# fcu-display.net
KiCad netlist of a schematic drawn in EAGLE
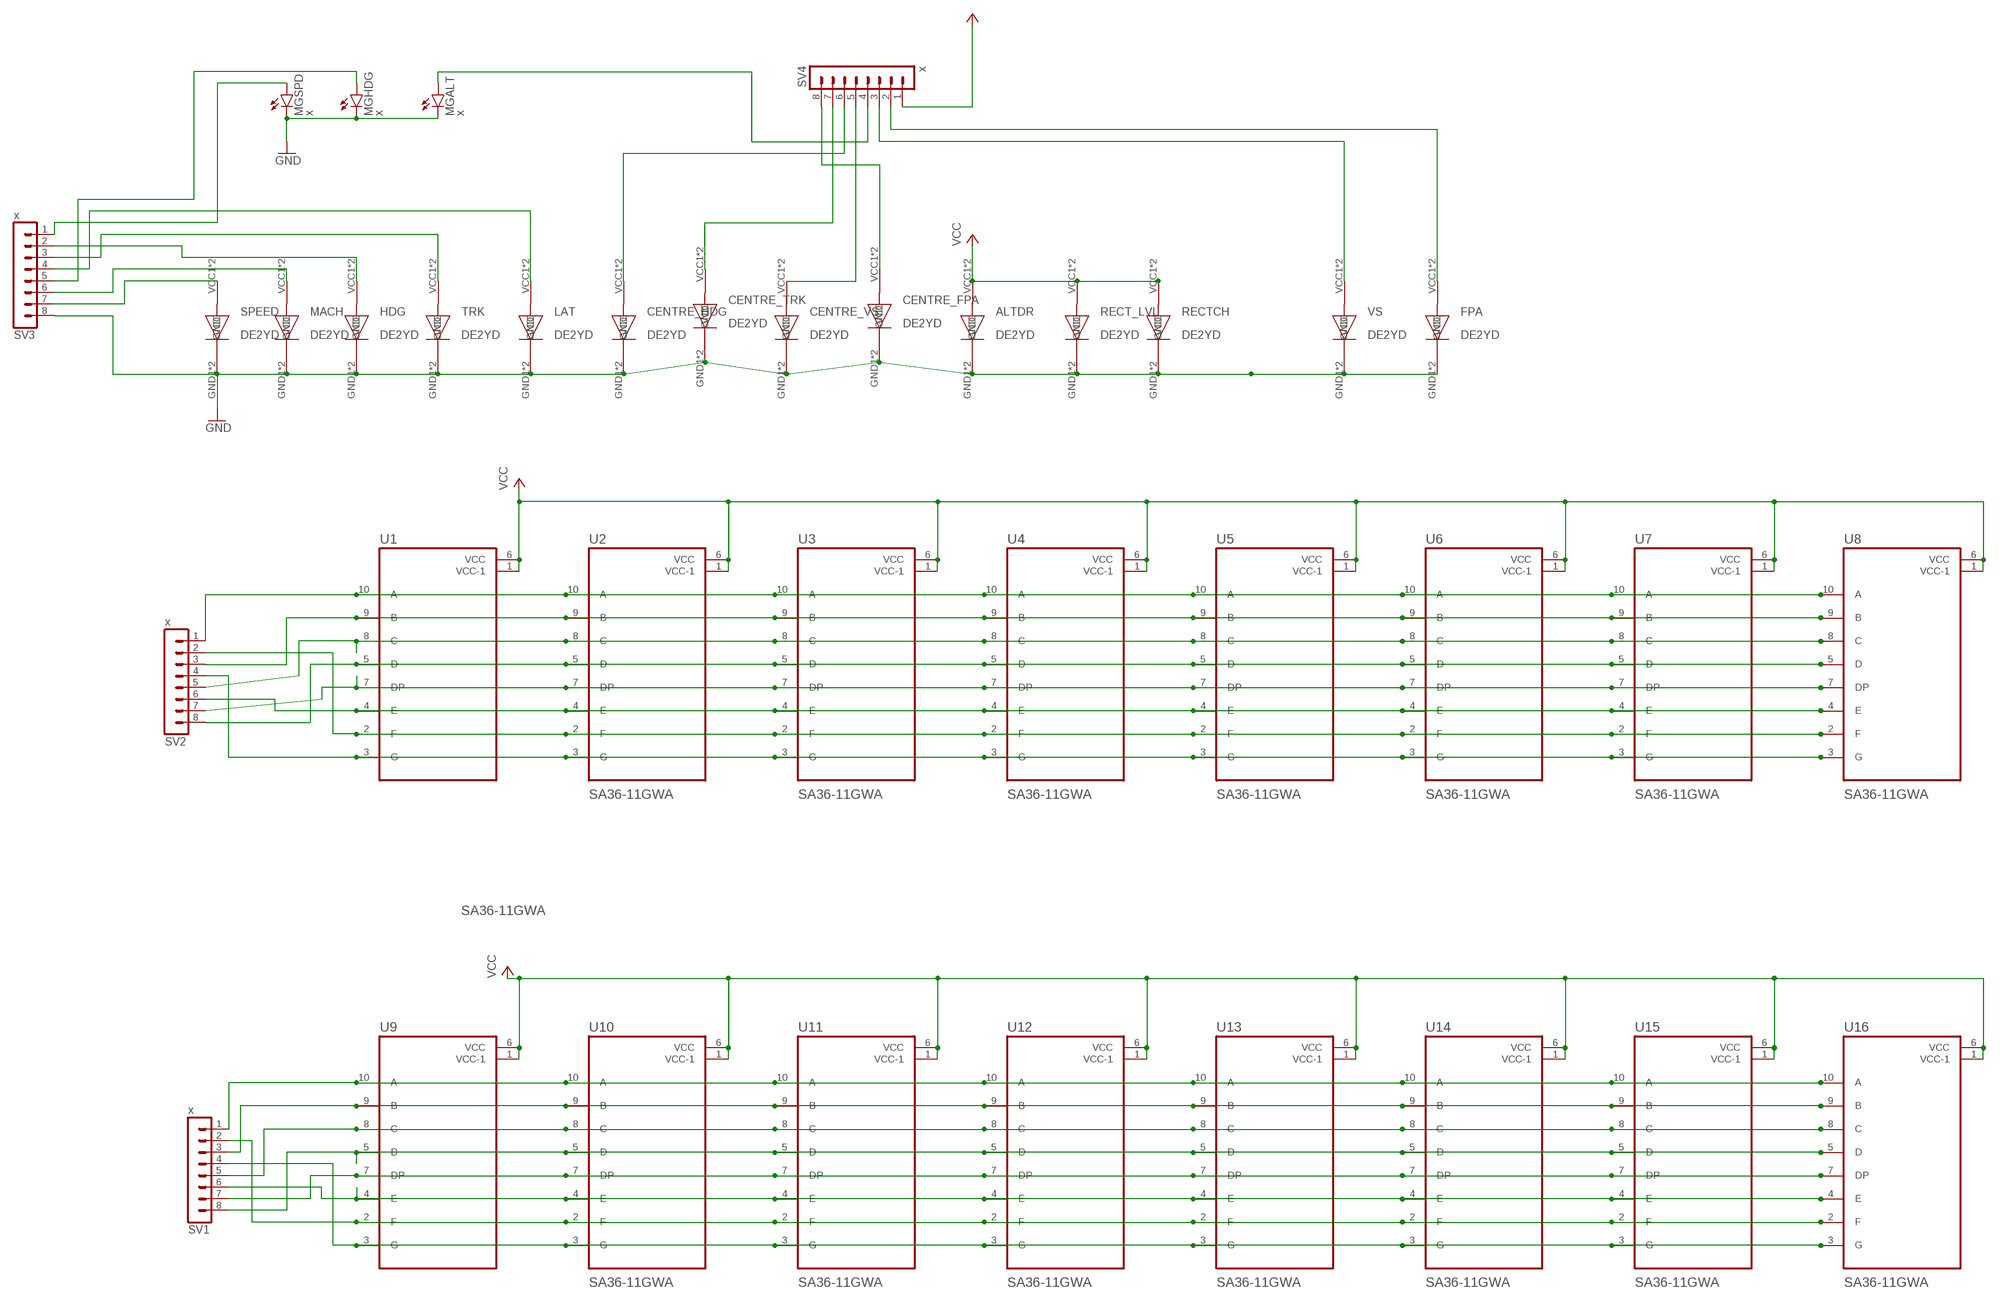
[diagram p0: schematic, sheet 1]

(export (version "E")
  (design (tool "Eeschema 10.0.6"))
  (components
    (comp (ref "ALTDR")
      (value "DE2YD")
      (footprint "eagle-import:STANDARD")
      (libsource (lib "eagle-import") (part "DE2YD"))
    )
    (comp (ref "CENTRE_FPA")
      (value "DE2YD")
      (footprint "eagle-import:STANDARD")
      (libsource (lib "eagle-import") (part "DE2YD"))
    )
    (comp (ref "CENTRE_HDG")
      (value "DE2YD")
      (footprint "eagle-import:STANDARD")
      (libsource (lib "eagle-import") (part "DE2YD"))
    )
    (comp (ref "CENTRE_TRK")
      (value "DE2YD")
      (footprint "eagle-import:STANDARD")
      (libsource (lib "eagle-import") (part "DE2YD"))
    )
    (comp (ref "CENTRE_VS")
      (value "DE2YD")
      (footprint "eagle-import:STANDARD")
      (libsource (lib "eagle-import") (part "DE2YD"))
    )
    (comp (ref "FPA")
      (value "DE2YD")
      (footprint "eagle-import:STANDARD")
      (libsource (lib "eagle-import") (part "DE2YD"))
    )
    (comp (ref "HDG")
      (value "DE2YD")
      (footprint "eagle-import:STANDARD")
      (libsource (lib "eagle-import") (part "DE2YD"))
    )
    (comp (ref "LAT")
      (value "DE2YD")
      (footprint "eagle-import:STANDARD")
      (libsource (lib "eagle-import") (part "DE2YD"))
    )
    (comp (ref "MACH")
      (value "DE2YD")
      (footprint "eagle-import:STANDARD")
      (libsource (lib "eagle-import") (part "DE2YD"))
    )
    (comp (ref "MGALT")
      (value "x")
      (footprint "eagle-import:LED3MM")
      (libsource (lib "eagle-import") (part "LED3MM"))
    )
    (comp (ref "MGHDG")
      (value "x")
      (footprint "eagle-import:LED3MM")
      (libsource (lib "eagle-import") (part "LED3MM"))
    )
    (comp (ref "MGSPD")
      (value "x")
      (footprint "eagle-import:LED3MM")
      (libsource (lib "eagle-import") (part "LED3MM"))
    )
    (comp (ref "RECTCH")
      (value "DE2YD")
      (footprint "eagle-import:STANDARD")
      (libsource (lib "eagle-import") (part "DE2YD"))
    )
    (comp (ref "RECT_LVL")
      (value "DE2YD")
      (footprint "eagle-import:STANDARD")
      (libsource (lib "eagle-import") (part "DE2YD"))
    )
    (comp (ref "SPEED")
      (value "DE2YD")
      (footprint "eagle-import:STANDARD")
      (libsource (lib "eagle-import") (part "DE2YD"))
    )
    (comp (ref "SV1")
      (value "x")
      (footprint "eagle-import:MA08-1")
      (libsource (lib "eagle-import") (part "MA08-1"))
    )
    (comp (ref "SV2")
      (value "x")
      (footprint "eagle-import:MA08-1")
      (libsource (lib "eagle-import") (part "MA08-1"))
    )
    (comp (ref "SV3")
      (value "x")
      (footprint "eagle-import:MA08-1")
      (libsource (lib "eagle-import") (part "MA08-1"))
    )
    (comp (ref "SV4")
      (value "x")
      (footprint "eagle-import:MA08-1")
      (libsource (lib "eagle-import") (part "MA08-1"))
    )
    (comp (ref "TRK")
      (value "DE2YD")
      (footprint "eagle-import:STANDARD")
      (libsource (lib "eagle-import") (part "DE2YD"))
    )
    (comp (ref "U1")
      (value "SA36-11GWA")
      (footprint "eagle-import:KINGBRIGHT_SC36-11SRWA")
      (fields (field (name "MF") "Kingbright"))
      (libsource (lib "eagle-import") (part "SA36-11GWA"))
    )
    (comp (ref "U2")
      (value "SA36-11GWA")
      (footprint "eagle-import:KINGBRIGHT_SC36-11SRWA")
      (fields (field (name "MF") "Kingbright"))
      (libsource (lib "eagle-import") (part "SA36-11GWA"))
    )
    (comp (ref "U3")
      (value "SA36-11GWA")
      (footprint "eagle-import:KINGBRIGHT_SC36-11SRWA")
      (fields (field (name "MF") "Kingbright"))
      (libsource (lib "eagle-import") (part "SA36-11GWA"))
    )
    (comp (ref "U4")
      (value "SA36-11GWA")
      (footprint "eagle-import:KINGBRIGHT_SC36-11SRWA")
      (fields (field (name "MF") "Kingbright"))
      (libsource (lib "eagle-import") (part "SA36-11GWA"))
    )
    (comp (ref "U5")
      (value "SA36-11GWA")
      (footprint "eagle-import:KINGBRIGHT_SC36-11SRWA")
      (fields (field (name "MF") "Kingbright"))
      (libsource (lib "eagle-import") (part "SA36-11GWA"))
    )
    (comp (ref "U6")
      (value "SA36-11GWA")
      (footprint "eagle-import:KINGBRIGHT_SC36-11SRWA")
      (fields (field (name "MF") "Kingbright"))
      (libsource (lib "eagle-import") (part "SA36-11GWA"))
    )
    (comp (ref "U7")
      (value "SA36-11GWA")
      (footprint "eagle-import:KINGBRIGHT_SC36-11SRWA")
      (fields (field (name "MF") "Kingbright"))
      (libsource (lib "eagle-import") (part "SA36-11GWA"))
    )
    (comp (ref "U8")
      (value "SA36-11GWA")
      (footprint "eagle-import:KINGBRIGHT_SC36-11SRWA")
      (fields (field (name "MF") "Kingbright"))
      (libsource (lib "eagle-import") (part "SA36-11GWA"))
    )
    (comp (ref "U9")
      (value "SA36-11GWA")
      (footprint "eagle-import:KINGBRIGHT_SC36-11SRWA")
      (fields (field (name "MF") "Kingbright"))
      (libsource (lib "eagle-import") (part "SA36-11GWA"))
    )
    (comp (ref "U10")
      (value "SA36-11GWA")
      (footprint "eagle-import:KINGBRIGHT_SC36-11SRWA")
      (fields (field (name "MF") "Kingbright"))
      (libsource (lib "eagle-import") (part "SA36-11GWA"))
    )
    (comp (ref "U11")
      (value "SA36-11GWA")
      (footprint "eagle-import:KINGBRIGHT_SC36-11SRWA")
      (fields (field (name "MF") "Kingbright"))
      (libsource (lib "eagle-import") (part "SA36-11GWA"))
    )
    (comp (ref "U12")
      (value "SA36-11GWA")
      (footprint "eagle-import:KINGBRIGHT_SC36-11SRWA")
      (fields (field (name "MF") "Kingbright"))
      (libsource (lib "eagle-import") (part "SA36-11GWA"))
    )
    (comp (ref "U13")
      (value "SA36-11GWA")
      (footprint "eagle-import:KINGBRIGHT_SC36-11SRWA")
      (fields (field (name "MF") "Kingbright"))
      (libsource (lib "eagle-import") (part "SA36-11GWA"))
    )
    (comp (ref "U14")
      (value "SA36-11GWA")
      (footprint "eagle-import:KINGBRIGHT_SC36-11SRWA")
      (fields (field (name "MF") "Kingbright"))
      (libsource (lib "eagle-import") (part "SA36-11GWA"))
    )
    (comp (ref "U15")
      (value "SA36-11GWA")
      (footprint "eagle-import:KINGBRIGHT_SC36-11SRWA")
      (fields (field (name "MF") "Kingbright"))
      (libsource (lib "eagle-import") (part "SA36-11GWA"))
    )
    (comp (ref "U16")
      (value "SA36-11GWA")
      (footprint "eagle-import:KINGBRIGHT_SC36-11SRWA")
      (fields (field (name "MF") "Kingbright"))
      (libsource (lib "eagle-import") (part "SA36-11GWA"))
    )
    (comp (ref "VS")
      (value "DE2YD")
      (footprint "eagle-import:STANDARD")
      (libsource (lib "eagle-import") (part "DE2YD"))
    )
  )
  (nets
    (net (code "1") (name "GND") (class "Default")
      (node (ref "ALTDR") (pin "GND1") (pinfunction "GND_GND1") (pintype "bidirectional"))
      (node (ref "ALTDR") (pin "GND2") (pinfunction "GND_GND2") (pintype "bidirectional"))
      (node (ref "CENTRE_FPA") (pin "GND1") (pinfunction "GND_GND1") (pintype "bidirectional"))
      (node (ref "CENTRE_FPA") (pin "GND2") (pinfunction "GND_GND2") (pintype "bidirectional"))
      (node (ref "CENTRE_HDG") (pin "GND1") (pinfunction "GND_GND1") (pintype "bidirectional"))
      (node (ref "CENTRE_HDG") (pin "GND2") (pinfunction "GND_GND2") (pintype "bidirectional"))
      (node (ref "CENTRE_TRK") (pin "GND1") (pinfunction "GND_GND1") (pintype "bidirectional"))
      (node (ref "CENTRE_TRK") (pin "GND2") (pinfunction "GND_GND2") (pintype "bidirectional"))
      (node (ref "CENTRE_VS") (pin "GND1") (pinfunction "GND_GND1") (pintype "bidirectional"))
      (node (ref "CENTRE_VS") (pin "GND2") (pinfunction "GND_GND2") (pintype "bidirectional"))
      (node (ref "FPA") (pin "GND1") (pinfunction "GND_GND1") (pintype "bidirectional"))
      (node (ref "FPA") (pin "GND2") (pinfunction "GND_GND2") (pintype "bidirectional"))
      (node (ref "HDG") (pin "GND1") (pinfunction "GND_GND1") (pintype "bidirectional"))
      (node (ref "HDG") (pin "GND2") (pinfunction "GND_GND2") (pintype "bidirectional"))
      (node (ref "LAT") (pin "GND1") (pinfunction "GND_GND1") (pintype "bidirectional"))
      (node (ref "LAT") (pin "GND2") (pinfunction "GND_GND2") (pintype "bidirectional"))
      (node (ref "MACH") (pin "GND1") (pinfunction "GND_GND1") (pintype "bidirectional"))
      (node (ref "MACH") (pin "GND2") (pinfunction "GND_GND2") (pintype "bidirectional"))
      (node (ref "MGALT") (pin "K") (pinfunction "C_K") (pintype "passive"))
      (node (ref "MGHDG") (pin "K") (pinfunction "C_K") (pintype "passive"))
      (node (ref "MGSPD") (pin "K") (pinfunction "C_K") (pintype "passive"))
      (node (ref "RECTCH") (pin "GND1") (pinfunction "GND_GND1") (pintype "bidirectional"))
      (node (ref "RECTCH") (pin "GND2") (pinfunction "GND_GND2") (pintype "bidirectional"))
      (node (ref "RECT_LVL") (pin "GND1") (pinfunction "GND_GND1") (pintype "bidirectional"))
      (node (ref "RECT_LVL") (pin "GND2") (pinfunction "GND_GND2") (pintype "bidirectional"))
      (node (ref "SPEED") (pin "GND1") (pinfunction "GND_GND1") (pintype "bidirectional"))
      (node (ref "SPEED") (pin "GND2") (pinfunction "GND_GND2") (pintype "bidirectional"))
      (node (ref "SV3") (pin "8") (pinfunction "8_8") (pintype "passive"))
      (node (ref "TRK") (pin "GND1") (pinfunction "GND_GND1") (pintype "bidirectional"))
      (node (ref "TRK") (pin "GND2") (pinfunction "GND_GND2") (pintype "bidirectional"))
      (node (ref "VS") (pin "GND1") (pinfunction "GND_GND1") (pintype "bidirectional"))
      (node (ref "VS") (pin "GND2") (pinfunction "GND_GND2") (pintype "bidirectional"))
    )
    (net (code "2") (name "Net-(CENTRE_FPA-VCC-PadVCC1)") (class "Default")
      (node (ref "CENTRE_FPA") (pin "VCC1") (pinfunction "VCC_VCC1") (pintype "bidirectional"))
      (node (ref "CENTRE_FPA") (pin "VCC2") (pinfunction "VCC_VCC2") (pintype "bidirectional"))
      (node (ref "SV4") (pin "8") (pinfunction "8_8") (pintype "passive"))
    )
    (net (code "3") (name "Net-(CENTRE_HDG-VCC-PadVCC1)") (class "Default")
      (node (ref "CENTRE_HDG") (pin "VCC1") (pinfunction "VCC_VCC1") (pintype "bidirectional"))
      (node (ref "CENTRE_HDG") (pin "VCC2") (pinfunction "VCC_VCC2") (pintype "bidirectional"))
      (node (ref "SV4") (pin "6") (pinfunction "6_6") (pintype "passive"))
    )
    (net (code "4") (name "Net-(CENTRE_TRK-VCC-PadVCC1)") (class "Default")
      (node (ref "CENTRE_TRK") (pin "VCC1") (pinfunction "VCC_VCC1") (pintype "bidirectional"))
      (node (ref "CENTRE_TRK") (pin "VCC2") (pinfunction "VCC_VCC2") (pintype "bidirectional"))
      (node (ref "SV4") (pin "7") (pinfunction "7_7") (pintype "passive"))
    )
    (net (code "5") (name "Net-(CENTRE_VS-VCC-PadVCC1)") (class "Default")
      (node (ref "CENTRE_VS") (pin "VCC1") (pinfunction "VCC_VCC1") (pintype "bidirectional"))
      (node (ref "CENTRE_VS") (pin "VCC2") (pinfunction "VCC_VCC2") (pintype "bidirectional"))
      (node (ref "SV4") (pin "5") (pinfunction "5_5") (pintype "passive"))
    )
    (net (code "6") (name "Net-(FPA-VCC-PadVCC1)") (class "Default")
      (node (ref "FPA") (pin "VCC1") (pinfunction "VCC_VCC1") (pintype "bidirectional"))
      (node (ref "FPA") (pin "VCC2") (pinfunction "VCC_VCC2") (pintype "bidirectional"))
      (node (ref "SV4") (pin "2") (pinfunction "2_2") (pintype "passive"))
    )
    (net (code "7") (name "Net-(HDG-VCC-PadVCC1)") (class "Default")
      (node (ref "HDG") (pin "VCC1") (pinfunction "VCC_VCC1") (pintype "bidirectional"))
      (node (ref "HDG") (pin "VCC2") (pinfunction "VCC_VCC2") (pintype "bidirectional"))
      (node (ref "SV3") (pin "2") (pinfunction "2_2") (pintype "passive"))
    )
    (net (code "8") (name "Net-(LAT-VCC-PadVCC1)") (class "Default")
      (node (ref "LAT") (pin "VCC1") (pinfunction "VCC_VCC1") (pintype "bidirectional"))
      (node (ref "LAT") (pin "VCC2") (pinfunction "VCC_VCC2") (pintype "bidirectional"))
      (node (ref "SV3") (pin "4") (pinfunction "4_4") (pintype "passive"))
    )
    (net (code "9") (name "Net-(MACH-VCC-PadVCC1)") (class "Default")
      (node (ref "MACH") (pin "VCC1") (pinfunction "VCC_VCC1") (pintype "bidirectional"))
      (node (ref "MACH") (pin "VCC2") (pinfunction "VCC_VCC2") (pintype "bidirectional"))
      (node (ref "SV3") (pin "6") (pinfunction "6_6") (pintype "passive"))
    )
    (net (code "10") (name "Net-(MGALT-PadA)") (class "Default")
      (node (ref "MGALT") (pin "A") (pinfunction "A_A") (pintype "passive"))
      (node (ref "SV4") (pin "4") (pinfunction "4_4") (pintype "passive"))
    )
    (net (code "11") (name "Net-(MGHDG-PadA)") (class "Default")
      (node (ref "MGHDG") (pin "A") (pinfunction "A_A") (pintype "passive"))
      (node (ref "SV3") (pin "5") (pinfunction "5_5") (pintype "passive"))
    )
    (net (code "12") (name "Net-(MGSPD-PadA)") (class "Default")
      (node (ref "MGSPD") (pin "A") (pinfunction "A_A") (pintype "passive"))
      (node (ref "SV3") (pin "1") (pinfunction "1_1") (pintype "passive"))
    )
    (net (code "13") (name "Net-(SPEED-VCC-PadVCC1)") (class "Default")
      (node (ref "SPEED") (pin "VCC1") (pinfunction "VCC_VCC1") (pintype "bidirectional"))
      (node (ref "SPEED") (pin "VCC2") (pinfunction "VCC_VCC2") (pintype "bidirectional"))
      (node (ref "SV3") (pin "7") (pinfunction "7_7") (pintype "passive"))
    )
    (net (code "14") (name "Net-(SV3-Pad3)") (class "Default")
      (node (ref "SV3") (pin "3") (pinfunction "3_3") (pintype "passive"))
      (node (ref "TRK") (pin "VCC1") (pinfunction "VCC_VCC1") (pintype "bidirectional"))
      (node (ref "TRK") (pin "VCC2") (pinfunction "VCC_VCC2") (pintype "bidirectional"))
    )
    (net (code "15") (name "Net-(SV4-Pad3)") (class "Default")
      (node (ref "SV4") (pin "3") (pinfunction "3_3") (pintype "passive"))
      (node (ref "VS") (pin "VCC1") (pinfunction "VCC_VCC1") (pintype "bidirectional"))
      (node (ref "VS") (pin "VCC2") (pinfunction "VCC_VCC2") (pintype "bidirectional"))
    )
    (net (code "16") (name "Net-(U1-A)") (class "Default")
      (node (ref "SV2") (pin "1") (pinfunction "1_1") (pintype "passive"))
      (node (ref "U1") (pin "10") (pinfunction "A_10") (pintype "bidirectional"))
      (node (ref "U2") (pin "10") (pinfunction "A_10") (pintype "bidirectional"))
      (node (ref "U3") (pin "10") (pinfunction "A_10") (pintype "bidirectional"))
      (node (ref "U4") (pin "10") (pinfunction "A_10") (pintype "bidirectional"))
      (node (ref "U5") (pin "10") (pinfunction "A_10") (pintype "bidirectional"))
      (node (ref "U6") (pin "10") (pinfunction "A_10") (pintype "bidirectional"))
      (node (ref "U7") (pin "10") (pinfunction "A_10") (pintype "bidirectional"))
      (node (ref "U8") (pin "10") (pinfunction "A_10") (pintype "bidirectional"))
    )
    (net (code "17") (name "Net-(U1-B)") (class "Default")
      (node (ref "SV2") (pin "3") (pinfunction "3_3") (pintype "passive"))
      (node (ref "U1") (pin "9") (pinfunction "B_9") (pintype "bidirectional"))
      (node (ref "U2") (pin "9") (pinfunction "B_9") (pintype "bidirectional"))
      (node (ref "U3") (pin "9") (pinfunction "B_9") (pintype "bidirectional"))
      (node (ref "U4") (pin "9") (pinfunction "B_9") (pintype "bidirectional"))
      (node (ref "U5") (pin "9") (pinfunction "B_9") (pintype "bidirectional"))
      (node (ref "U6") (pin "9") (pinfunction "B_9") (pintype "bidirectional"))
      (node (ref "U7") (pin "9") (pinfunction "B_9") (pintype "bidirectional"))
      (node (ref "U8") (pin "9") (pinfunction "B_9") (pintype "bidirectional"))
    )
    (net (code "18") (name "Net-(U1-C)") (class "Default")
      (node (ref "SV2") (pin "5") (pinfunction "5_5") (pintype "passive"))
      (node (ref "U1") (pin "8") (pinfunction "C_8") (pintype "bidirectional"))
      (node (ref "U2") (pin "8") (pinfunction "C_8") (pintype "bidirectional"))
      (node (ref "U3") (pin "8") (pinfunction "C_8") (pintype "bidirectional"))
      (node (ref "U4") (pin "8") (pinfunction "C_8") (pintype "bidirectional"))
      (node (ref "U5") (pin "8") (pinfunction "C_8") (pintype "bidirectional"))
      (node (ref "U6") (pin "8") (pinfunction "C_8") (pintype "bidirectional"))
      (node (ref "U7") (pin "8") (pinfunction "C_8") (pintype "bidirectional"))
      (node (ref "U8") (pin "8") (pinfunction "C_8") (pintype "bidirectional"))
    )
    (net (code "19") (name "Net-(U1-D)") (class "Default")
      (node (ref "SV2") (pin "8") (pinfunction "8_8") (pintype "passive"))
      (node (ref "U1") (pin "5") (pinfunction "D_5") (pintype "bidirectional"))
      (node (ref "U2") (pin "5") (pinfunction "D_5") (pintype "bidirectional"))
      (node (ref "U3") (pin "5") (pinfunction "D_5") (pintype "bidirectional"))
      (node (ref "U4") (pin "5") (pinfunction "D_5") (pintype "bidirectional"))
      (node (ref "U5") (pin "5") (pinfunction "D_5") (pintype "bidirectional"))
      (node (ref "U6") (pin "5") (pinfunction "D_5") (pintype "bidirectional"))
      (node (ref "U7") (pin "5") (pinfunction "D_5") (pintype "bidirectional"))
      (node (ref "U8") (pin "5") (pinfunction "D_5") (pintype "bidirectional"))
    )
    (net (code "20") (name "Net-(U1-DP)") (class "Default")
      (node (ref "SV2") (pin "7") (pinfunction "7_7") (pintype "passive"))
      (node (ref "U1") (pin "7") (pinfunction "DP_7") (pintype "bidirectional"))
      (node (ref "U2") (pin "7") (pinfunction "DP_7") (pintype "bidirectional"))
      (node (ref "U3") (pin "7") (pinfunction "DP_7") (pintype "bidirectional"))
      (node (ref "U4") (pin "7") (pinfunction "DP_7") (pintype "bidirectional"))
      (node (ref "U5") (pin "7") (pinfunction "DP_7") (pintype "bidirectional"))
      (node (ref "U6") (pin "7") (pinfunction "DP_7") (pintype "bidirectional"))
      (node (ref "U7") (pin "7") (pinfunction "DP_7") (pintype "bidirectional"))
      (node (ref "U8") (pin "7") (pinfunction "DP_7") (pintype "bidirectional"))
    )
    (net (code "21") (name "Net-(U1-E)") (class "Default")
      (node (ref "SV2") (pin "6") (pinfunction "6_6") (pintype "passive"))
      (node (ref "U1") (pin "4") (pinfunction "E_4") (pintype "bidirectional"))
      (node (ref "U2") (pin "4") (pinfunction "E_4") (pintype "bidirectional"))
      (node (ref "U3") (pin "4") (pinfunction "E_4") (pintype "bidirectional"))
      (node (ref "U4") (pin "4") (pinfunction "E_4") (pintype "bidirectional"))
      (node (ref "U5") (pin "4") (pinfunction "E_4") (pintype "bidirectional"))
      (node (ref "U6") (pin "4") (pinfunction "E_4") (pintype "bidirectional"))
      (node (ref "U7") (pin "4") (pinfunction "E_4") (pintype "bidirectional"))
      (node (ref "U8") (pin "4") (pinfunction "E_4") (pintype "bidirectional"))
    )
    (net (code "22") (name "Net-(U1-F)") (class "Default")
      (node (ref "SV2") (pin "2") (pinfunction "2_2") (pintype "passive"))
      (node (ref "U1") (pin "2") (pinfunction "F_2") (pintype "bidirectional"))
      (node (ref "U2") (pin "2") (pinfunction "F_2") (pintype "bidirectional"))
      (node (ref "U3") (pin "2") (pinfunction "F_2") (pintype "bidirectional"))
      (node (ref "U4") (pin "2") (pinfunction "F_2") (pintype "bidirectional"))
      (node (ref "U5") (pin "2") (pinfunction "F_2") (pintype "bidirectional"))
      (node (ref "U6") (pin "2") (pinfunction "F_2") (pintype "bidirectional"))
      (node (ref "U7") (pin "2") (pinfunction "F_2") (pintype "bidirectional"))
      (node (ref "U8") (pin "2") (pinfunction "F_2") (pintype "bidirectional"))
    )
    (net (code "23") (name "Net-(U1-G)") (class "Default")
      (node (ref "SV2") (pin "4") (pinfunction "4_4") (pintype "passive"))
      (node (ref "U1") (pin "3") (pinfunction "G_3") (pintype "bidirectional"))
      (node (ref "U2") (pin "3") (pinfunction "G_3") (pintype "bidirectional"))
      (node (ref "U3") (pin "3") (pinfunction "G_3") (pintype "bidirectional"))
      (node (ref "U4") (pin "3") (pinfunction "G_3") (pintype "bidirectional"))
      (node (ref "U5") (pin "3") (pinfunction "G_3") (pintype "bidirectional"))
      (node (ref "U6") (pin "3") (pinfunction "G_3") (pintype "bidirectional"))
      (node (ref "U7") (pin "3") (pinfunction "G_3") (pintype "bidirectional"))
      (node (ref "U8") (pin "3") (pinfunction "G_3") (pintype "bidirectional"))
    )
    (net (code "24") (name "Net-(U10-A)") (class "Default")
      (node (ref "SV1") (pin "1") (pinfunction "1_1") (pintype "passive"))
      (node (ref "U10") (pin "10") (pinfunction "A_10") (pintype "bidirectional"))
      (node (ref "U11") (pin "10") (pinfunction "A_10") (pintype "bidirectional"))
      (node (ref "U12") (pin "10") (pinfunction "A_10") (pintype "bidirectional"))
      (node (ref "U13") (pin "10") (pinfunction "A_10") (pintype "bidirectional"))
      (node (ref "U14") (pin "10") (pinfunction "A_10") (pintype "bidirectional"))
      (node (ref "U15") (pin "10") (pinfunction "A_10") (pintype "bidirectional"))
      (node (ref "U16") (pin "10") (pinfunction "A_10") (pintype "bidirectional"))
      (node (ref "U9") (pin "10") (pinfunction "A_10") (pintype "bidirectional"))
    )
    (net (code "25") (name "Net-(U10-B)") (class "Default")
      (node (ref "SV1") (pin "3") (pinfunction "3_3") (pintype "passive"))
      (node (ref "U10") (pin "9") (pinfunction "B_9") (pintype "bidirectional"))
      (node (ref "U11") (pin "9") (pinfunction "B_9") (pintype "bidirectional"))
      (node (ref "U12") (pin "9") (pinfunction "B_9") (pintype "bidirectional"))
      (node (ref "U13") (pin "9") (pinfunction "B_9") (pintype "bidirectional"))
      (node (ref "U14") (pin "9") (pinfunction "B_9") (pintype "bidirectional"))
      (node (ref "U15") (pin "9") (pinfunction "B_9") (pintype "bidirectional"))
      (node (ref "U16") (pin "9") (pinfunction "B_9") (pintype "bidirectional"))
      (node (ref "U9") (pin "9") (pinfunction "B_9") (pintype "bidirectional"))
    )
    (net (code "26") (name "Net-(U10-C)") (class "Default")
      (node (ref "SV1") (pin "5") (pinfunction "5_5") (pintype "passive"))
      (node (ref "U10") (pin "8") (pinfunction "C_8") (pintype "bidirectional"))
      (node (ref "U11") (pin "8") (pinfunction "C_8") (pintype "bidirectional"))
      (node (ref "U12") (pin "8") (pinfunction "C_8") (pintype "bidirectional"))
      (node (ref "U13") (pin "8") (pinfunction "C_8") (pintype "bidirectional"))
      (node (ref "U14") (pin "8") (pinfunction "C_8") (pintype "bidirectional"))
      (node (ref "U15") (pin "8") (pinfunction "C_8") (pintype "bidirectional"))
      (node (ref "U16") (pin "8") (pinfunction "C_8") (pintype "bidirectional"))
      (node (ref "U9") (pin "8") (pinfunction "C_8") (pintype "bidirectional"))
    )
    (net (code "27") (name "Net-(U10-D)") (class "Default")
      (node (ref "SV1") (pin "8") (pinfunction "8_8") (pintype "passive"))
      (node (ref "U10") (pin "5") (pinfunction "D_5") (pintype "bidirectional"))
      (node (ref "U11") (pin "5") (pinfunction "D_5") (pintype "bidirectional"))
      (node (ref "U12") (pin "5") (pinfunction "D_5") (pintype "bidirectional"))
      (node (ref "U13") (pin "5") (pinfunction "D_5") (pintype "bidirectional"))
      (node (ref "U14") (pin "5") (pinfunction "D_5") (pintype "bidirectional"))
      (node (ref "U15") (pin "5") (pinfunction "D_5") (pintype "bidirectional"))
      (node (ref "U16") (pin "5") (pinfunction "D_5") (pintype "bidirectional"))
      (node (ref "U9") (pin "5") (pinfunction "D_5") (pintype "bidirectional"))
    )
    (net (code "28") (name "Net-(U10-DP)") (class "Default")
      (node (ref "SV1") (pin "7") (pinfunction "7_7") (pintype "passive"))
      (node (ref "U10") (pin "7") (pinfunction "DP_7") (pintype "bidirectional"))
      (node (ref "U11") (pin "7") (pinfunction "DP_7") (pintype "bidirectional"))
      (node (ref "U12") (pin "7") (pinfunction "DP_7") (pintype "bidirectional"))
      (node (ref "U13") (pin "7") (pinfunction "DP_7") (pintype "bidirectional"))
      (node (ref "U14") (pin "7") (pinfunction "DP_7") (pintype "bidirectional"))
      (node (ref "U15") (pin "7") (pinfunction "DP_7") (pintype "bidirectional"))
      (node (ref "U16") (pin "7") (pinfunction "DP_7") (pintype "bidirectional"))
      (node (ref "U9") (pin "7") (pinfunction "DP_7") (pintype "bidirectional"))
    )
    (net (code "29") (name "Net-(U10-E)") (class "Default")
      (node (ref "SV1") (pin "6") (pinfunction "6_6") (pintype "passive"))
      (node (ref "U10") (pin "4") (pinfunction "E_4") (pintype "bidirectional"))
      (node (ref "U11") (pin "4") (pinfunction "E_4") (pintype "bidirectional"))
      (node (ref "U12") (pin "4") (pinfunction "E_4") (pintype "bidirectional"))
      (node (ref "U13") (pin "4") (pinfunction "E_4") (pintype "bidirectional"))
      (node (ref "U14") (pin "4") (pinfunction "E_4") (pintype "bidirectional"))
      (node (ref "U15") (pin "4") (pinfunction "E_4") (pintype "bidirectional"))
      (node (ref "U16") (pin "4") (pinfunction "E_4") (pintype "bidirectional"))
      (node (ref "U9") (pin "4") (pinfunction "E_4") (pintype "bidirectional"))
    )
    (net (code "30") (name "Net-(U10-F)") (class "Default")
      (node (ref "SV1") (pin "2") (pinfunction "2_2") (pintype "passive"))
      (node (ref "U10") (pin "2") (pinfunction "F_2") (pintype "bidirectional"))
      (node (ref "U11") (pin "2") (pinfunction "F_2") (pintype "bidirectional"))
      (node (ref "U12") (pin "2") (pinfunction "F_2") (pintype "bidirectional"))
      (node (ref "U13") (pin "2") (pinfunction "F_2") (pintype "bidirectional"))
      (node (ref "U14") (pin "2") (pinfunction "F_2") (pintype "bidirectional"))
      (node (ref "U15") (pin "2") (pinfunction "F_2") (pintype "bidirectional"))
      (node (ref "U16") (pin "2") (pinfunction "F_2") (pintype "bidirectional"))
      (node (ref "U9") (pin "2") (pinfunction "F_2") (pintype "bidirectional"))
    )
    (net (code "31") (name "Net-(U10-G)") (class "Default")
      (node (ref "SV1") (pin "4") (pinfunction "4_4") (pintype "passive"))
      (node (ref "U10") (pin "3") (pinfunction "G_3") (pintype "bidirectional"))
      (node (ref "U11") (pin "3") (pinfunction "G_3") (pintype "bidirectional"))
      (node (ref "U12") (pin "3") (pinfunction "G_3") (pintype "bidirectional"))
      (node (ref "U13") (pin "3") (pinfunction "G_3") (pintype "bidirectional"))
      (node (ref "U14") (pin "3") (pinfunction "G_3") (pintype "bidirectional"))
      (node (ref "U15") (pin "3") (pinfunction "G_3") (pintype "bidirectional"))
      (node (ref "U16") (pin "3") (pinfunction "G_3") (pintype "bidirectional"))
      (node (ref "U9") (pin "3") (pinfunction "G_3") (pintype "bidirectional"))
    )
    (net (code "32") (name "VCC") (class "Default")
      (node (ref "ALTDR") (pin "VCC1") (pinfunction "VCC_VCC1") (pintype "bidirectional"))
      (node (ref "ALTDR") (pin "VCC2") (pinfunction "VCC_VCC2") (pintype "bidirectional"))
      (node (ref "RECTCH") (pin "VCC1") (pinfunction "VCC_VCC1") (pintype "bidirectional"))
      (node (ref "RECTCH") (pin "VCC2") (pinfunction "VCC_VCC2") (pintype "bidirectional"))
      (node (ref "RECT_LVL") (pin "VCC1") (pinfunction "VCC_VCC1") (pintype "bidirectional"))
      (node (ref "RECT_LVL") (pin "VCC2") (pinfunction "VCC_VCC2") (pintype "bidirectional"))
      (node (ref "SV4") (pin "1") (pinfunction "1_1") (pintype "passive"))
      (node (ref "U1") (pin "1") (pinfunction "VCC-1_1") (pintype "power_in"))
      (node (ref "U1") (pin "6") (pinfunction "VCC_6") (pintype "power_in"))
      (node (ref "U10") (pin "1") (pinfunction "VCC-1_1") (pintype "power_in"))
      (node (ref "U10") (pin "6") (pinfunction "VCC_6") (pintype "power_in"))
      (node (ref "U11") (pin "1") (pinfunction "VCC-1_1") (pintype "power_in"))
      (node (ref "U11") (pin "6") (pinfunction "VCC_6") (pintype "power_in"))
      (node (ref "U12") (pin "1") (pinfunction "VCC-1_1") (pintype "power_in"))
      (node (ref "U12") (pin "6") (pinfunction "VCC_6") (pintype "power_in"))
      (node (ref "U13") (pin "1") (pinfunction "VCC-1_1") (pintype "power_in"))
      (node (ref "U13") (pin "6") (pinfunction "VCC_6") (pintype "power_in"))
      (node (ref "U14") (pin "1") (pinfunction "VCC-1_1") (pintype "power_in"))
      (node (ref "U14") (pin "6") (pinfunction "VCC_6") (pintype "power_in"))
      (node (ref "U15") (pin "1") (pinfunction "VCC-1_1") (pintype "power_in"))
      (node (ref "U15") (pin "6") (pinfunction "VCC_6") (pintype "power_in"))
      (node (ref "U16") (pin "1") (pinfunction "VCC-1_1") (pintype "power_in"))
      (node (ref "U16") (pin "6") (pinfunction "VCC_6") (pintype "power_in"))
      (node (ref "U2") (pin "1") (pinfunction "VCC-1_1") (pintype "power_in"))
      (node (ref "U2") (pin "6") (pinfunction "VCC_6") (pintype "power_in"))
      (node (ref "U3") (pin "1") (pinfunction "VCC-1_1") (pintype "power_in"))
      (node (ref "U3") (pin "6") (pinfunction "VCC_6") (pintype "power_in"))
      (node (ref "U4") (pin "1") (pinfunction "VCC-1_1") (pintype "power_in"))
      (node (ref "U4") (pin "6") (pinfunction "VCC_6") (pintype "power_in"))
      (node (ref "U5") (pin "1") (pinfunction "VCC-1_1") (pintype "power_in"))
      (node (ref "U5") (pin "6") (pinfunction "VCC_6") (pintype "power_in"))
      (node (ref "U6") (pin "1") (pinfunction "VCC-1_1") (pintype "power_in"))
      (node (ref "U6") (pin "6") (pinfunction "VCC_6") (pintype "power_in"))
      (node (ref "U7") (pin "1") (pinfunction "VCC-1_1") (pintype "power_in"))
      (node (ref "U7") (pin "6") (pinfunction "VCC_6") (pintype "power_in"))
      (node (ref "U8") (pin "1") (pinfunction "VCC-1_1") (pintype "power_in"))
      (node (ref "U8") (pin "6") (pinfunction "VCC_6") (pintype "power_in"))
      (node (ref "U9") (pin "1") (pinfunction "VCC-1_1") (pintype "power_in"))
      (node (ref "U9") (pin "6") (pinfunction "VCC_6") (pintype "power_in"))
    )
  )
)
